# VoltageRegulator_3v3.net
KiCad netlist of a schematic drawn in Altium Designer
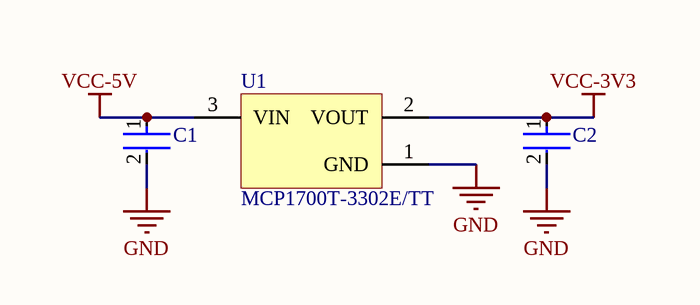
[diagram p0: VoltageRegulator_3v3.SchDoc]

(export (version "E")
  (design (tool "Eeschema 10.0.6"))
  (components
    (comp (ref "C1")
      (value "CL10A105KO8NNNC")
      (footprint "FP-CL10-IPC_A")
      (description "Cap Ceramic 1uF 16V X5R ±10% Pad SMD 0603 +85°C T/R")
      (fields (field (name "TOLERANCE") "10%") (field (name "VOLTAGE") "16V"))
      (libsource (lib "Altium Content Vault") (part "b4654b650e69147ec39a6b967a45e02"))
    )
    (comp (ref "C2")
      (value "CL10A105KO8NNNC")
      (footprint "FP-CL10-IPC_A")
      (description "Cap Ceramic 1uF 16V X5R ±10% Pad SMD 0603 +85°C T/R")
      (fields (field (name "TOLERANCE") "10%") (field (name "VOLTAGE") "16V"))
      (libsource (lib "Altium Content Vault") (part "b4654b650e69147ec39a6b967a45e02"))
    )
    (comp (ref "U1")
      (value "MCP1700T-3302E/TT")
      (footprint "SOT-23-TT3_N")
      (description "Low Quiescent Current LDO, 3-Pin SOT-23, Extended Temperature, Tape and Reel")
      (libsource (lib "Altium Content Vault") (part "PM-LINEREG-MCP1700-IL3"))
    )
  )
  (nets
    (net (code "1") (name "GND") (class "Default")
      (node (ref "C1") (pin "2") (pinfunction "2_2") (pintype "passive"))
      (node (ref "C2") (pin "2") (pinfunction "2_2") (pintype "passive"))
      (node (ref "U1") (pin "1") (pinfunction "GND_1") (pintype "power_in"))
    )
    (net (code "2") (name "VCC-3V3") (class "Default")
      (node (ref "C2") (pin "1") (pinfunction "1_1") (pintype "passive"))
      (node (ref "U1") (pin "2") (pinfunction "VOUT_2") (pintype "power_in"))
    )
    (net (code "3") (name "VCC-5V") (class "Default")
      (node (ref "C1") (pin "1") (pinfunction "1_1") (pintype "passive"))
      (node (ref "U1") (pin "3") (pinfunction "VIN_3") (pintype "power_in"))
    )
  )
)
